# High-Speed-Line-Follower.net
KiCad netlist of a schematic drawn in Altium Designer
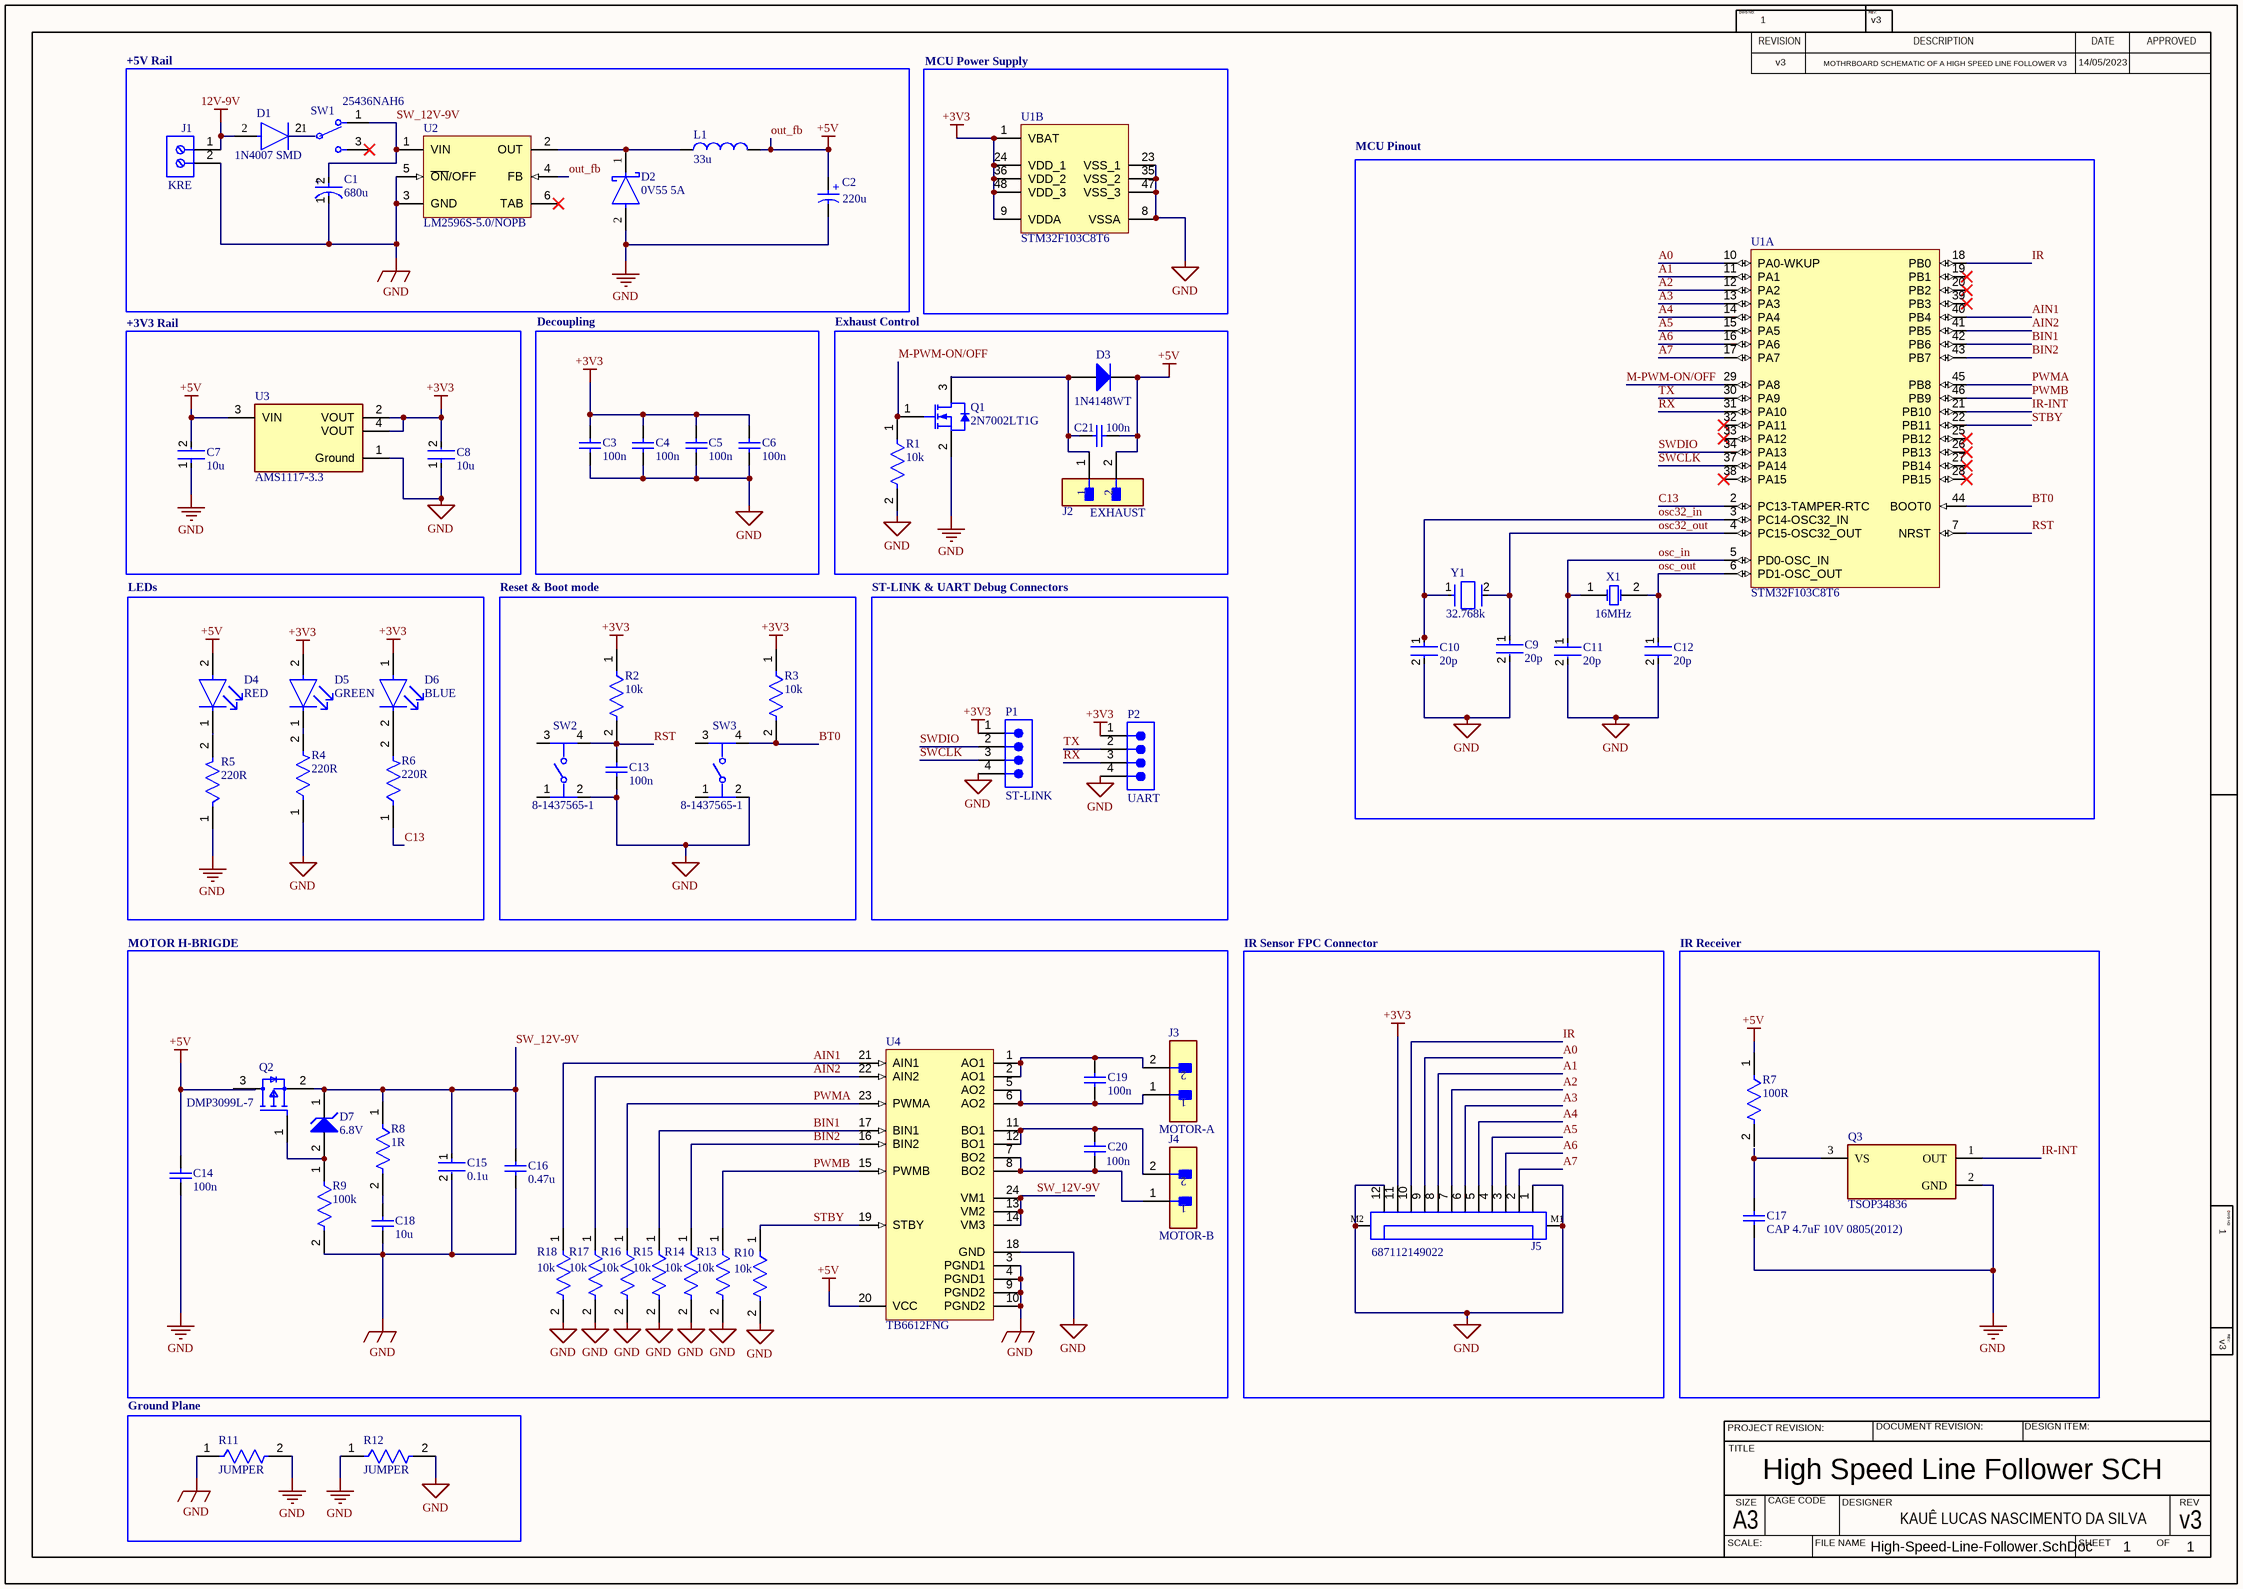
[diagram p0: High-Speed-Line-Follower.SchDoc]

(export (version "E")
  (design (tool "Eeschema 10.0.6"))
  (components
    (comp (ref "C1")
      (value "680u")
      (footprint "FP-OS-CON-SMT-E12-MFG")
      (description "Conductive Polymer Aluminum Solid Capacitors (OS-CON) 680uF ±20% 16V")
      (fields (field (name "TOLERANCE") "20%"))
      (libsource (lib "Altium Content Vault") (part "a00bbbee19879c290e62620ae7e47b1"))
    )
    (comp (ref "C2")
      (value "220u")
      (footprint "WCAP-ASLI_D6.3H7.7")
      (description "WCAP-ASLI Aluminum Electrolytic Capacitors")
      (libsource (lib "Altium Content Vault") (part "Capacitor_Polarized"))
    )
    (comp (ref "C3")
      (value "100n")
      (footprint "CAPC2013X145X50ML20T20")
      (fields (field (name "MANUFACTURER") "Vitramon") (field (name "PART NUMBER") "VJ0805Y104JXXCW1BC"))
      (libsource (lib "Altium Content Vault") (part "CAP"))
    )
    (comp (ref "C4")
      (value "100n")
      (footprint "CAPC2013X145X50ML20T20")
      (fields (field (name "MANUFACTURER") "Vitramon") (field (name "PART NUMBER") "VJ0805Y104JXXCW1BC"))
      (libsource (lib "Altium Content Vault") (part "CAP"))
    )
    (comp (ref "C5")
      (value "100n")
      (footprint "CAPC2013X145X50ML20T20")
      (fields (field (name "MANUFACTURER") "Vitramon") (field (name "PART NUMBER") "VJ0805Y104JXXCW1BC"))
      (libsource (lib "Altium Content Vault") (part "CAP"))
    )
    (comp (ref "C6")
      (value "100n")
      (footprint "CAPC2013X145X50ML20T20")
      (fields (field (name "MANUFACTURER") "Vitramon") (field (name "PART NUMBER") "VJ0805Y104JXXCW1BC"))
      (libsource (lib "Altium Content Vault") (part "CAP"))
    )
    (comp (ref "C7")
      (value "10u")
      (footprint "FP-C0805C106K8RACAUTO-MFG")
      (description "CAP CER 10UF 10V X7R 0805")
      (fields (field (name "TOLERANCE") "10%"))
      (libsource (lib "Altium Content Vault") (part "b4654b650e69147ec39a6b967a45e02"))
    )
    (comp (ref "C8")
      (value "10u")
      (footprint "FP-C0805C106K8RACAUTO-MFG")
      (description "CAP CER 10UF 10V X7R 0805")
      (fields (field (name "TOLERANCE") "10%"))
      (libsource (lib "Altium Content Vault") (part "b4654b650e69147ec39a6b967a45e02"))
    )
    (comp (ref "C9")
      (value "20p")
      (footprint "FP-C0805C-DN-MFG")
      (description "C0805 20 pF X8R 30ppm/°C 2.00% 10 V")
      (fields
        (field (name "OCTOPART") "https://octopart.com/c0805c200g8hactu-kemet-88726762")
        (field (name "TOLERANCE") "0.02")
      )
      (libsource (lib "Altium Content Vault") (part "b4654b650e69147ec39a6b967a45e02"))
    )
    (comp (ref "C10")
      (value "20p")
      (footprint "FP-C0805C-DN-MFG")
      (description "C0805 20 pF X8R 30ppm/°C 2.00% 10 V")
      (fields
        (field (name "OCTOPART") "https://octopart.com/c0805c200g8hactu-kemet-88726762")
        (field (name "TOLERANCE") "0.02")
      )
      (libsource (lib "Altium Content Vault") (part "b4654b650e69147ec39a6b967a45e02"))
    )
    (comp (ref "C11")
      (value "20p")
      (footprint "FP-C0805C-DN-MFG")
      (description "C0805 20 pF X8R 30ppm/°C 2.00% 10 V")
      (fields
        (field (name "OCTOPART") "https://octopart.com/c0805c200g8hactu-kemet-88726762")
        (field (name "TOLERANCE") "0.02")
      )
      (libsource (lib "Altium Content Vault") (part "b4654b650e69147ec39a6b967a45e02"))
    )
    (comp (ref "C12")
      (value "20p")
      (footprint "FP-C0805C-DN-MFG")
      (description "C0805 20 pF X8R 30ppm/°C 2.00% 10 V")
      (fields
        (field (name "OCTOPART") "https://octopart.com/c0805c200g8hactu-kemet-88726762")
        (field (name "TOLERANCE") "0.02")
      )
      (libsource (lib "Altium Content Vault") (part "b4654b650e69147ec39a6b967a45e02"))
    )
    (comp (ref "C13")
      (value "100n")
      (footprint "CAPC2013X140X45LL15T25")
      (fields (field (name "PART NUMBER") "GCM21BR71E104KA37L") (field (name "MANUFACTURER") "Murata"))
      (libsource (lib "Altium Content Vault") (part "CAP"))
    )
    (comp (ref "C14")
      (value "100n")
      (footprint "CAPC2013X140X45LL15T25")
      (fields (field (name "PART NUMBER") "GCM21BR71E104KA37L") (field (name "MANUFACTURER") "Murata"))
      (libsource (lib "Altium Content Vault") (part "CAP"))
    )
    (comp (ref "C15")
      (value "0.1u")
      (footprint "FP-C0805C-DN-MFG")
      (description "CAP CER 0.1UF 50V X7R 0805")
      (fields
        (field (name "MANUFACTURER PART NUMBER") "C0805C104K5RACTU")
        (field (name "MANUFACTURER") "KEMET")
      )
      (libsource (lib "Altium Content Vault") (part "b4654b650e69147ec39a6b967a45e02"))
    )
    (comp (ref "C16")
      (value "0.47u")
      (footprint "CAPC2013X140X50ML20T25")
      (fields (field (name "PART NUMBER") "C0805C474K3NACTU") (field (name "MANUFACTURER") "Kemet"))
      (libsource (lib "Altium Content Vault") (part "CAP"))
    )
    (comp (ref "C17")
      (value "CAP 4.7uF 10V 0805(2012)")
      (footprint "CAPC0805(2012)155_L")
      (description "CAP 4.7uF 10V ±10% 0805 (2012 Metric) Thickness 1.55mm SMD")
      (fields (field (name "TOLERANCE") "Â±10%"))
      (libsource (lib "Altium Content Vault") (part "CAP"))
    )
    (comp (ref "C18")
      (value "10u")
      (footprint "CAPC2013X145X50ML20T25")
      (fields (field (name "PART NUMBER") "C0805C106M4PACTU") (field (name "MANUFACTURER") "Kemet"))
      (libsource (lib "Altium Content Vault") (part "CAP"))
    )
    (comp (ref "C19")
      (value "100n")
      (footprint "CAPC2013X140X45LL15T25")
      (fields (field (name "PART NUMBER") "GCM21BR71E104KA37L") (field (name "MANUFACTURER") "Murata"))
      (libsource (lib "Altium Content Vault") (part "CAP"))
    )
    (comp (ref "C20")
      (value "100n")
      (footprint "CAPC2013X140X45LL15T25")
      (fields (field (name "PART NUMBER") "GCM21BR71E104KA37L") (field (name "MANUFACTURER") "Murata"))
      (libsource (lib "Altium Content Vault") (part "CAP"))
    )
    (comp (ref "C21")
      (value "100n")
      (footprint "CAPC2013X140X45LL15T25")
      (fields (field (name "PART NUMBER") "GCM21BR71E104KA37L") (field (name "MANUFACTURER") "Murata"))
      (libsource (lib "Altium Content Vault") (part "CAP"))
    )
    (comp (ref "D1")
      (value "1N4007 SMD")
      (footprint "FP-1N4007_SMD-IPC_C")
      (description "Rectifier, 1Kv, 1A, Do-214Ac Rohs Compliant: Yes")
      (libsource (lib "Altium Content Vault") (part "d7152d700b627762746794eb795d46e"))
    )
    (comp (ref "D2")
      (value "0V55 5A")
      (footprint "FP-DO-214AA-MFG")
      (description "5819SMJE3/TR13 Rectifier Diode, Schottky, 1 Phase, 1 Element, 1A, 40V V(RRM), Silicon")
      (libsource (lib "Altium Content Vault") (part "1d6ec82d83fb6aee721767c19dac4b9"))
    )
    (comp (ref "D3")
      (value "1N4148WT")
      (footprint "FAIR-SOD-523F-2_V")
      (description "High Conductance Fast Switching Diode, 75 V, -55 to 150 degC, 2-Pin SOD523F, RoHS")
      (fields (field (name "MANUFACTURER") "Fairchild Semiconductor"))
      (libsource (lib "Altium Content Vault") (part "FAIR-D_K1A2-2"))
    )
    (comp (ref "D4")
      (value "RED")
      (footprint "FP-SML-LXT0805IW-TR-MFG")
      (description "LED RED DIFFUSED SMD")
      (libsource (lib "Altium Content Vault") (part "8706943c75ba83719d021d2fdc84c58"))
    )
    (comp (ref "D5")
      (value "GREEN")
      (footprint "FP-LTST-C171GKT-MFG")
      (description "LED GREEN CLEAR CHIP SMD")
      (libsource (lib "Altium Content Vault") (part "8706943c75ba83719d021d2fdc84c58"))
    )
    (comp (ref "D6")
      (value "BLUE")
      (footprint "FP-SM0805UBWC-MFG")
      (description "LED BLUE CLEAR 0805 SMD")
      (libsource (lib "Altium Content Vault") (part "ab1c01a81903e929fc6c44469aada92"))
    )
    (comp (ref "D7")
      (value "6.8V")
      (footprint "ONSC-SMB-2-403A-03_H_V")
      (description "3 W Zener Voltage Regulator, 2-Pin SMB, Pb-Free, Tape and Reel")
      (fields (field (name "PARTNUMBER") "1SMB5921BT3G") (field (name "MANUFACTURER") "On Semiconductor"))
      (libsource (lib "Altium Content Vault") (part "ONSC-K1A2-2"))
    )
    (comp (ref "J1")
      (value "KRE")
      (footprint "691502710002")
      (description "Terminal Block, Wtb, 2Way, 22-14Awg Rohs Compliant: Yes")
      (libsource (lib "Altium Content Vault") (part "TBL - 1R - 02P - Screw"))
    )
    (comp (ref "J2")
      (value "EXHAUST")
      (footprint "FP-B2B-XH-A_LF_SN-MFG")
      (description "CONN HEADER VERT 2POS 2.5MM")
      (libsource (lib "Altium Content Vault") (part "3bc925449376181038e59eaffc5286c"))
    )
    (comp (ref "J3")
      (value "MOTOR-A")
      (footprint "FP-B2B-XH-A_LF_SN-MFG")
      (description "CONN HEADER VERT 2POS 2.5MM")
      (libsource (lib "") (part "3bc925449376181038e59eaffc5286c_1"))
    )
    (comp (ref "J4")
      (value "MOTOR-B")
      (footprint "FP-B2B-XH-A_LF_SN-MFG")
      (description "CONN HEADER VERT 2POS 2.5MM")
      (libsource (lib "") (part "3bc925449376181038e59eaffc5286c_1"))
    )
    (comp (ref "J5")
      (value "687112149022")
      (footprint "687112149022")
      (description "FFC/FPC Connector, 12 Contact(s), 1 Row(s), Female, Right Angle, Surface Mount Terminal")
      (libsource (lib "Altium Content Vault") (part "FPC - 12P - 2MP"))
    )
    (comp (ref "L1")
      (value "33u")
      (footprint "SUMI-CDRH127_V")
      (description "Power Inductor, 10 uH, +/- 20%, -40 to 100 degC, 2-Pin SMD, RoHS, Tape and Reel")
      (fields (field (name "MANUFACTURER") "Sumida") (field (name "TOLERANCE") "±20%"))
      (libsource (lib "Altium Content Vault") (part "IND-2"))
    )
    (comp (ref "P1")
      (value "ST-LINK")
      (footprint "61300411121")
      (description "THT Vertical Pin Header WR-PHD, Pitch 2.54 mm, Single Row, 4 pins")
      (libsource (lib "Altium Content Vault") (part "Header_Male_1R_04P"))
    )
    (comp (ref "P2")
      (value "UART")
      (footprint "61300411121")
      (description "THT Vertical Pin Header WR-PHD, Pitch 2.54 mm, Single Row, 4 pins")
      (libsource (lib "Altium Content Vault") (part "Header_Male_1R_04P"))
    )
    (comp (ref "Q1")
      (value "2N7002LT1G")
      (footprint "ONSC-SOT-23-3-318-08_V")
      (description "Small Signal MOSFET, 60 V, 115 mA, N-Channel, 3-Pin SOT-23, Pb-Free, Tape and Reel")
      (fields (field (name "MANUFACTURER") "On Semiconductor"))
      (libsource (lib "Altium Content Vault") (part "ONSC-NMOS-G1S2D3-3"))
    )
    (comp (ref "Q2")
      (value "DMP3099L-7")
      (footprint "FP-SOT23-IPC_B")
      (description "MOSFET P-CH 30V SOT23")
      (libsource (lib "Altium Content Vault") (part "d876440acba04c58a9f817a20952145"))
    )
    (comp (ref "Q3")
      (value "TSOP34836")
      (footprint "FP-6_550-5169_01-4-MFG")
      (description "TSOP34836 TSOP348 Series 2.5 to 5.5 V 36 KHz 350 uA 45 m Side View IR Receiver")
      (libsource (lib "Altium Content Vault") (part "e5e79ff3c4dc99b7cd60a318e631326"))
    )
    (comp (ref "R1")
      (value "10k")
      (footprint "FP-CRGCQ0805-IPC_C")
      (description "CRGCQ 0805 10K 5%")
      (fields
        (field (name "MANUFACTURER PART NUMBER") "CRGCQ0805J10K")
        (field (name "MANUFACTURER") "TE Connectivity")
      )
      (libsource (lib "Altium Content Vault") (part "1029c3af85768c4190bb7ad29bc67b5"))
    )
    (comp (ref "R2")
      (value "10k")
      (footprint "FP-CRGCQ0805-IPC_C")
      (description "CRGCQ 0805 10K 5%")
      (fields
        (field (name "MANUFACTURER PART NUMBER") "CRGCQ0805J10K")
        (field (name "MANUFACTURER") "TE Connectivity")
      )
      (libsource (lib "Altium Content Vault") (part "1029c3af85768c4190bb7ad29bc67b5"))
    )
    (comp (ref "R3")
      (value "10k")
      (footprint "FP-CRGCQ0805-IPC_C")
      (description "CRGCQ 0805 10K 5%")
      (fields
        (field (name "MANUFACTURER PART NUMBER") "CRGCQ0805J10K")
        (field (name "MANUFACTURER") "TE Connectivity")
      )
      (libsource (lib "Altium Content Vault") (part "1029c3af85768c4190bb7ad29bc67b5"))
    )
    (comp (ref "R4")
      (value "220R")
      (footprint "FP-AC0805-MFG")
      (description "RES SMD 220 OHM 1% 1/8W 0805")
      (fields
        (field (name "OCTOPART") "https://octopart.com/ac0805fr-07220rl-yageo-26041145")
        (field (name "TOLERANCE") "0.01")
      )
      (libsource (lib "Altium Content Vault") (part "1029c3af85768c4190bb7ad29bc67b5"))
    )
    (comp (ref "R5")
      (value "220R")
      (footprint "FP-AC0805-MFG")
      (description "RES SMD 220 OHM 1% 1/8W 0805")
      (fields
        (field (name "OCTOPART") "https://octopart.com/ac0805fr-07220rl-yageo-26041145")
        (field (name "TOLERANCE") "0.01")
      )
      (libsource (lib "Altium Content Vault") (part "1029c3af85768c4190bb7ad29bc67b5"))
    )
    (comp (ref "R6")
      (value "220R")
      (footprint "FP-AC0805-MFG")
      (description "RES SMD 220 OHM 1% 1/8W 0805")
      (fields
        (field (name "OCTOPART") "https://octopart.com/ac0805fr-07220rl-yageo-26041145")
        (field (name "TOLERANCE") "0.01")
      )
      (libsource (lib "Altium Content Vault") (part "1029c3af85768c4190bb7ad29bc67b5"))
    )
    (comp (ref "R7")
      (value "100R")
      (footprint "FP-CRCW0805-HPe3-IPC_C")
      (description "RES Thick Film, 100Ω, 5%, 0.5W, 200ppm/°C, 0805")
      (fields (field (name "TOLERANCE") "5%"))
      (libsource (lib "Altium Content Vault") (part "1029c3af85768c4190bb7ad29bc67b5"))
    )
    (comp (ref "R8")
      (value "1R")
      (footprint "FP-CRCW0805-e3-IPC_C")
      (description "RES Thick Film, 1Ω, 5%, 0.125W, 200ppm/°C, 0805")
      (fields (field (name "TOLERANCE") "5%"))
      (libsource (lib "Altium Content Vault") (part "1029c3af85768c4190bb7ad29bc67b5"))
    )
    (comp (ref "R9")
      (value "100k")
      (footprint "FP-MCU0805-IPC_C")
      (description "RES 1.05K OHM 0.5% 1/5W 0805")
      (fields (field (name "TOLERANCE") "1%"))
      (libsource (lib "Altium Content Vault") (part "1029c3af85768c4190bb7ad29bc67b5"))
    )
    (comp (ref "R10")
      (value "10k")
      (footprint "FP-CRGCQ0805-IPC_C")
      (description "CRGCQ 0805 10K 5%")
      (fields
        (field (name "MANUFACTURER PART NUMBER") "CRGCQ0805J10K")
        (field (name "MANUFACTURER") "TE Connectivity")
      )
      (libsource (lib "Altium Content Vault") (part "1029c3af85768c4190bb7ad29bc67b5"))
    )
    (comp (ref "R11")
      (value "JUMPER")
      (footprint "FP-HCJ0805-MFG")
      (description "RES 0 OHM JUMPER 1/2W 0805")
      (libsource (lib "Altium Content Vault") (part "1029c3af85768c4190bb7ad29bc67b5"))
    )
    (comp (ref "R12")
      (value "JUMPER")
      (footprint "FP-HCJ0805-MFG")
      (description "RES 0 OHM JUMPER 1/2W 0805")
      (libsource (lib "Altium Content Vault") (part "1029c3af85768c4190bb7ad29bc67b5"))
    )
    (comp (ref "R13")
      (value "10k")
      (footprint "FP-CRGCQ0805-IPC_C")
      (description "CRGCQ 0805 10K 5%")
      (fields
        (field (name "MANUFACTURER PART NUMBER") "CRGCQ0805J10K")
        (field (name "MANUFACTURER") "TE Connectivity")
      )
      (libsource (lib "Altium Content Vault") (part "1029c3af85768c4190bb7ad29bc67b5"))
    )
    (comp (ref "R14")
      (value "10k")
      (footprint "FP-CRGCQ0805-IPC_C")
      (description "CRGCQ 0805 10K 5%")
      (fields
        (field (name "MANUFACTURER PART NUMBER") "CRGCQ0805J10K")
        (field (name "MANUFACTURER") "TE Connectivity")
      )
      (libsource (lib "Altium Content Vault") (part "1029c3af85768c4190bb7ad29bc67b5"))
    )
    (comp (ref "R15")
      (value "10k")
      (footprint "FP-CRGCQ0805-IPC_C")
      (description "CRGCQ 0805 10K 5%")
      (fields
        (field (name "MANUFACTURER PART NUMBER") "CRGCQ0805J10K")
        (field (name "MANUFACTURER") "TE Connectivity")
      )
      (libsource (lib "Altium Content Vault") (part "1029c3af85768c4190bb7ad29bc67b5"))
    )
    (comp (ref "R16")
      (value "10k")
      (footprint "FP-CRGCQ0805-IPC_C")
      (description "CRGCQ 0805 10K 5%")
      (fields
        (field (name "MANUFACTURER PART NUMBER") "CRGCQ0805J10K")
        (field (name "MANUFACTURER") "TE Connectivity")
      )
      (libsource (lib "Altium Content Vault") (part "1029c3af85768c4190bb7ad29bc67b5"))
    )
    (comp (ref "R17")
      (value "10k")
      (footprint "FP-CRGCQ0805-IPC_C")
      (description "CRGCQ 0805 10K 5%")
      (fields
        (field (name "MANUFACTURER PART NUMBER") "CRGCQ0805J10K")
        (field (name "MANUFACTURER") "TE Connectivity")
      )
      (libsource (lib "Altium Content Vault") (part "1029c3af85768c4190bb7ad29bc67b5"))
    )
    (comp (ref "R18")
      (value "10k")
      (footprint "FP-CRGCQ0805-IPC_C")
      (description "CRGCQ 0805 10K 5%")
      (fields
        (field (name "MANUFACTURER PART NUMBER") "CRGCQ0805J10K")
        (field (name "MANUFACTURER") "TE Connectivity")
      )
      (libsource (lib "Altium Content Vault") (part "1029c3af85768c4190bb7ad29bc67b5"))
    )
    (comp (ref "SW1")
      (value "25436NAH6")
      (footprint "FP-25436NAH6-MFG")
      (description "SWITCH SLIDE SPDT 4A 125V")
      (libsource (lib "Altium Content Vault") (part "52c419afdc2a387c7d548259a9aeefb"))
    )
    (comp (ref "SW2")
      (value "8-1437565-1")
      (footprint "FP-8-1437565-1-MFG")
      (description "SWITCH TACTILE SPST-NO 0.02A 15V")
      (libsource (lib "Altium Content Vault") (part "b8895f3f4cefb76e1819d2863dba89b"))
    )
    (comp (ref "SW3")
      (value "8-1437565-1")
      (footprint "FP-8-1437565-1-MFG")
      (description "SWITCH TACTILE SPST-NO 0.02A 15V")
      (libsource (lib "Altium Content Vault") (part "b8895f3f4cefb76e1819d2863dba89b"))
    )
    (comp (ref "U1")
      (value "STM32F103C8T6")
      (footprint "STM-LQFP48_L")
      (libsource (lib "Altium Content Vault") (part "MC-ARM-STM32F103X8_B-SQ48"))
    )
    (comp (ref "U2")
      (value "LM2596S-5.0/NOPB")
      (footprint "KTT0005B_M")
      (description "SIMPLE SWITCHER® Power Converter 150 KHz 3A Step-Down Voltage Regulator, 5-pin TO-263, Pb-Free")
      (fields (field (name "MANUFACTURER") "Texas Instruments"))
      (libsource (lib "Altium Content Vault") (part "PM-REG-LM2575HVS-12"))
    )
    (comp (ref "U3")
      (value "AMS1117-3.3")
      (footprint "FP-AMS1117-IPC_C")
      (description "LDO Voltage Regulators 1A, 3.3V")
      (fields
        (field (name "OCTOPART") "https://octopart.com/ams1117-3.3-advanced+monolithic+systems-25899300")
        (field (name "MANUFACTURER") "Advanced Monolithic Systems")
      )
      (libsource (lib "Altium Content Vault") (part "8bdbb5f8e77002000e30dd2845d0354"))
    )
    (comp (ref "U4")
      (value "TB6612FNG")
      (footprint "TOSH-SSOP-24_M")
      (description "Driver IC for Dual DC Motor, 15 V, -20 to 85 degC, 24-Pin SSOP, RoHS, Tape and Reel")
      (libsource (lib "Altium Content Vault") (part "TOSH-TB6612FNG-SOP-24"))
    )
    (comp (ref "X1")
      (value "16MHz")
      (footprint "CTS-ATS-SM-XTAL-2")
      (description "ATS-SM Series Quartz Crystal, 16 MHz, -20 to 70 degC, 11.1 x 4.83 x 4.3mm SMD, RoHS, Tape and Reel")
      (fields (field (name "PARTNUMBER") "ATS16ASM-1") (field (name "MANUFACTURER") "CTS Corporation"))
      (libsource (lib "Altium Content Vault") (part "CTS-ATS-SM-XTAL-2"))
    )
    (comp (ref "Y1")
      (value "32.768k")
      (footprint "FP-NX2012SA-MFG")
      (description "CRYSTAL 32.7680KHZ 12.5PF SMD")
      (libsource (lib "Altium Content Vault") (part "c23a69dc6c9e2f18f2079038eb95dd1"))
    )
  )
  (nets
    (net (code "1") (name "+3V3") (class "Default")
      (node (ref "C3") (pin "2") (pinfunction "2_2") (pintype "passive"))
      (node (ref "C4") (pin "2") (pinfunction "2_2") (pintype "passive"))
      (node (ref "C5") (pin "2") (pinfunction "2_2") (pintype "passive"))
      (node (ref "C6") (pin "2") (pinfunction "2_2") (pintype "passive"))
      (node (ref "C8") (pin "2") (pinfunction "2_2") (pintype "passive"))
      (node (ref "D6") (pin "1") (pinfunction "A_1") (pintype "passive"))
      (node (ref "J5") (pin "11") (pinfunction "11_11") (pintype "passive"))
      (node (ref "P1") (pin "1") (pinfunction "1_1") (pintype "passive"))
      (node (ref "P2") (pin "1") (pinfunction "1_1") (pintype "passive"))
      (node (ref "R2") (pin "1") (pinfunction "1_1") (pintype "passive"))
      (node (ref "R3") (pin "1") (pinfunction "1_1") (pintype "passive"))
      (node (ref "U1") (pin "1") (pinfunction "VBAT_1") (pintype "power_in"))
      (node (ref "U1") (pin "24") (pinfunction "VDD_1_24") (pintype "power_in"))
      (node (ref "U1") (pin "36") (pinfunction "VDD_2_36") (pintype "power_in"))
      (node (ref "U1") (pin "48") (pinfunction "VDD_3_48") (pintype "power_in"))
      (node (ref "U1") (pin "9") (pinfunction "VDDA_9") (pintype "power_in"))
      (node (ref "U3") (pin "2") (pinfunction "VOUT_2") (pintype "passive"))
      (node (ref "U3") (pin "4") (pinfunction "VOUT_4") (pintype "passive"))
    )
    (net (code "2") (name "+5V") (class "Default")
      (node (ref "C14") (pin "2") (pinfunction "2_2") (pintype "passive"))
      (node (ref "C2") (pin "1") (pinfunction "P_1") (pintype "passive"))
      (node (ref "C21") (pin "1") (pinfunction "1_1") (pintype "passive"))
      (node (ref "C7") (pin "2") (pinfunction "2_2") (pintype "passive"))
      (node (ref "D3") (pin "1") (pinfunction "K_1") (pintype "passive"))
      (node (ref "D4") (pin "2") (pinfunction "A_2") (pintype "passive"))
      (node (ref "J2") (pin "2") (pinfunction "2_2") (pintype "passive"))
      (node (ref "L1") (pin "2") (pinfunction "2_2") (pintype "passive"))
      (node (ref "R7") (pin "1") (pinfunction "1_1") (pintype "passive"))
      (node (ref "U2") (pin "4") (pinfunction "FB_4") (pintype "input"))
      (node (ref "U3") (pin "3") (pinfunction "VIN_3") (pintype "power_in"))
      (node (ref "U4") (pin "20") (pinfunction "VCC_20") (pintype "power_in"))
    )
    (net (code "3") (name "/A0") (class "Default")
      (node (ref "J5") (pin "9") (pinfunction "9_9") (pintype "passive"))
      (node (ref "U1") (pin "10") (pinfunction "PA0-WKUP_10") (pintype "bidirectional"))
    )
    (net (code "4") (name "/A1") (class "Default")
      (node (ref "J5") (pin "8") (pinfunction "8_8") (pintype "passive"))
      (node (ref "U1") (pin "11") (pinfunction "PA1_11") (pintype "bidirectional"))
    )
    (net (code "5") (name "/A2") (class "Default")
      (node (ref "J5") (pin "7") (pinfunction "7_7") (pintype "passive"))
      (node (ref "U1") (pin "12") (pinfunction "PA2_12") (pintype "bidirectional"))
    )
    (net (code "6") (name "/A3") (class "Default")
      (node (ref "J5") (pin "6") (pinfunction "6_6") (pintype "passive"))
      (node (ref "U1") (pin "13") (pinfunction "PA3_13") (pintype "bidirectional"))
    )
    (net (code "7") (name "/A4") (class "Default")
      (node (ref "J5") (pin "5") (pinfunction "5_5") (pintype "passive"))
      (node (ref "U1") (pin "14") (pinfunction "PA4_14") (pintype "bidirectional"))
    )
    (net (code "8") (name "/A5") (class "Default")
      (node (ref "J5") (pin "4") (pinfunction "4_4") (pintype "passive"))
      (node (ref "U1") (pin "15") (pinfunction "PA5_15") (pintype "bidirectional"))
    )
    (net (code "9") (name "/A6") (class "Default")
      (node (ref "J5") (pin "3") (pinfunction "3_3") (pintype "passive"))
      (node (ref "U1") (pin "16") (pinfunction "PA6_16") (pintype "bidirectional"))
    )
    (net (code "10") (name "/A7") (class "Default")
      (node (ref "J5") (pin "2") (pinfunction "2_2") (pintype "passive"))
      (node (ref "U1") (pin "17") (pinfunction "PA7_17") (pintype "bidirectional"))
    )
    (net (code "11") (name "/AIN1") (class "Default")
      (node (ref "R18") (pin "1") (pinfunction "1_1") (pintype "passive"))
      (node (ref "U1") (pin "40") (pinfunction "PB4_40") (pintype "bidirectional"))
      (node (ref "U4") (pin "21") (pinfunction "AIN1_21") (pintype "input"))
    )
    (net (code "12") (name "/AIN2") (class "Default")
      (node (ref "R17") (pin "1") (pinfunction "1_1") (pintype "passive"))
      (node (ref "U1") (pin "41") (pinfunction "PB5_41") (pintype "bidirectional"))
      (node (ref "U4") (pin "22") (pinfunction "AIN2_22") (pintype "input"))
    )
    (net (code "13") (name "/BIN1") (class "Default")
      (node (ref "R15") (pin "1") (pinfunction "1_1") (pintype "passive"))
      (node (ref "U1") (pin "42") (pinfunction "PB6_42") (pintype "bidirectional"))
      (node (ref "U4") (pin "17") (pinfunction "BIN1_17") (pintype "input"))
    )
    (net (code "14") (name "/BIN2") (class "Default")
      (node (ref "R14") (pin "1") (pinfunction "1_1") (pintype "passive"))
      (node (ref "U1") (pin "43") (pinfunction "PB7_43") (pintype "bidirectional"))
      (node (ref "U4") (pin "16") (pinfunction "BIN2_16") (pintype "input"))
    )
    (net (code "15") (name "/BT0") (class "Default")
      (node (ref "R3") (pin "2") (pinfunction "2_2") (pintype "passive"))
      (node (ref "SW3") (pin "4") (pinfunction "4_4") (pintype "passive"))
      (node (ref "U1") (pin "44") (pinfunction "BOOT0_44") (pintype "input"))
    )
    (net (code "16") (name "/C13") (class "Default")
      (node (ref "R6") (pin "1") (pinfunction "1_1") (pintype "passive"))
      (node (ref "U1") (pin "2") (pinfunction "PC13-TAMPER-RTC_2") (pintype "bidirectional"))
    )
    (net (code "17") (name "/IR") (class "Default")
      (node (ref "J5") (pin "10") (pinfunction "10_10") (pintype "passive"))
      (node (ref "U1") (pin "18") (pinfunction "PB0_18") (pintype "bidirectional"))
    )
    (net (code "18") (name "/IR-INT") (class "Default")
      (node (ref "Q3") (pin "1") (pinfunction "OUT_1") (pintype "passive"))
      (node (ref "U1") (pin "21") (pinfunction "PB10_21") (pintype "bidirectional"))
    )
    (net (code "19") (name "/M-PWM-ON{slash}OFF") (class "Default")
      (node (ref "Q1") (pin "1") (pinfunction "G_1") (pintype "passive"))
      (node (ref "R1") (pin "1") (pinfunction "1_1") (pintype "passive"))
      (node (ref "U1") (pin "29") (pinfunction "PA8_29") (pintype "bidirectional"))
    )
    (net (code "20") (name "/PWMA") (class "Default")
      (node (ref "R16") (pin "1") (pinfunction "1_1") (pintype "passive"))
      (node (ref "U1") (pin "45") (pinfunction "PB8_45") (pintype "bidirectional"))
      (node (ref "U4") (pin "23") (pinfunction "PWMA_23") (pintype "input"))
    )
    (net (code "21") (name "/PWMB") (class "Default")
      (node (ref "R13") (pin "1") (pinfunction "1_1") (pintype "passive"))
      (node (ref "U1") (pin "46") (pinfunction "PB9_46") (pintype "bidirectional"))
      (node (ref "U4") (pin "15") (pinfunction "PWMB_15") (pintype "input"))
    )
    (net (code "22") (name "/RST") (class "Default")
      (node (ref "C13") (pin "2") (pinfunction "2_2") (pintype "passive"))
      (node (ref "R2") (pin "2") (pinfunction "2_2") (pintype "passive"))
      (node (ref "SW2") (pin "4") (pinfunction "4_4") (pintype "passive"))
      (node (ref "U1") (pin "7") (pinfunction "NRST_7") (pintype "bidirectional"))
    )
    (net (code "23") (name "/RX") (class "Default")
      (node (ref "P2") (pin "3") (pinfunction "3_3") (pintype "passive"))
      (node (ref "U1") (pin "31") (pinfunction "PA10_31") (pintype "bidirectional"))
    )
    (net (code "24") (name "/STBY") (class "Default")
      (node (ref "R10") (pin "1") (pinfunction "1_1") (pintype "passive"))
      (node (ref "U1") (pin "22") (pinfunction "PB11_22") (pintype "bidirectional"))
      (node (ref "U4") (pin "19") (pinfunction "STBY_19") (pintype "input"))
    )
    (net (code "25") (name "/SWCLK") (class "Default")
      (node (ref "P1") (pin "3") (pinfunction "3_3") (pintype "passive"))
      (node (ref "U1") (pin "37") (pinfunction "PA14_37") (pintype "bidirectional"))
    )
    (net (code "26") (name "/SWDIO") (class "Default")
      (node (ref "P1") (pin "2") (pinfunction "2_2") (pintype "passive"))
      (node (ref "U1") (pin "34") (pinfunction "PA13_34") (pintype "bidirectional"))
    )
    (net (code "27") (name "/SW_12V-9V") (class "Default")
      (node (ref "C1") (pin "2") (pinfunction "A_2") (pintype "passive"))
      (node (ref "C15") (pin "1") (pinfunction "1_1") (pintype "passive"))
      (node (ref "C16") (pin "2") (pinfunction "2_2") (pintype "passive"))
      (node (ref "D7") (pin "1") (pinfunction "K_1") (pintype "passive"))
      (node (ref "Q2") (pin "2") (pinfunction "S_2") (pintype "passive"))
      (node (ref "R8") (pin "1") (pinfunction "1_1") (pintype "passive"))
      (node (ref "SW1") (pin "1") (pinfunction "1_1") (pintype "passive"))
      (node (ref "U2") (pin "1") (pinfunction "VIN_1") (pintype "power_in"))
      (node (ref "U4") (pin "13") (pinfunction "VM2_13") (pintype "power_in"))
      (node (ref "U4") (pin "14") (pinfunction "VM3_14") (pintype "power_in"))
      (node (ref "U4") (pin "24") (pinfunction "VM1_24") (pintype "power_in"))
    )
    (net (code "28") (name "/TX") (class "Default")
      (node (ref "P2") (pin "2") (pinfunction "2_2") (pintype "passive"))
      (node (ref "U1") (pin "30") (pinfunction "PA9_30") (pintype "bidirectional"))
    )
    (net (code "29") (name "/osc32_in") (class "Default")
      (node (ref "C10") (pin "1") (pinfunction "1_1") (pintype "passive"))
      (node (ref "U1") (pin "3") (pinfunction "PC14-OSC32_IN_3") (pintype "bidirectional"))
      (node (ref "Y1") (pin "1") (pinfunction "1_1") (pintype "passive"))
    )
    (net (code "30") (name "/osc32_out") (class "Default")
      (node (ref "C9") (pin "1") (pinfunction "1_1") (pintype "passive"))
      (node (ref "U1") (pin "4") (pinfunction "PC15-OSC32_OUT_4") (pintype "bidirectional"))
      (node (ref "Y1") (pin "2") (pinfunction "2_2") (pintype "passive"))
    )
    (net (code "31") (name "/osc_in") (class "Default")
      (node (ref "C11") (pin "1") (pinfunction "1_1") (pintype "passive"))
      (node (ref "U1") (pin "5") (pinfunction "PD0-OSC_IN_5") (pintype "bidirectional"))
      (node (ref "X1") (pin "1") (pinfunction "X1_1") (pintype "passive"))
    )
    (net (code "32") (name "/osc_out") (class "Default")
      (node (ref "C12") (pin "1") (pinfunction "1_1") (pintype "passive"))
      (node (ref "U1") (pin "6") (pinfunction "PD1-OSC_OUT_6") (pintype "bidirectional"))
      (node (ref "X1") (pin "2") (pinfunction "X2_2") (pintype "passive"))
    )
    (net (code "33") (name "12V-9V") (class "Default")
      (node (ref "D1") (pin "2") (pinfunction "A_2") (pintype "passive"))
      (node (ref "J1") (pin "1") (pinfunction "1_1") (pintype "passive"))
    )
    (net (code "34") (name "GND") (class "Default")
      (node (ref "C1") (pin "1") (pinfunction "C_1") (pintype "passive"))
      (node (ref "C10") (pin "2") (pinfunction "2_2") (pintype "passive"))
      (node (ref "C11") (pin "2") (pinfunction "2_2") (pintype "passive"))
      (node (ref "C12") (pin "2") (pinfunction "2_2") (pintype "passive"))
      (node (ref "C13") (pin "1") (pinfunction "1_1") (pintype "passive"))
      (node (ref "C14") (pin "1") (pinfunction "1_1") (pintype "passive"))
      (node (ref "C15") (pin "2") (pinfunction "2_2") (pintype "passive"))
      (node (ref "C16") (pin "1") (pinfunction "1_1") (pintype "passive"))
      (node (ref "C17") (pin "1") (pinfunction "1_1") (pintype "passive"))
      (node (ref "C18") (pin "1") (pinfunction "1_1") (pintype "passive"))
      (node (ref "C2") (pin "2") (pinfunction "N_2") (pintype "passive"))
      (node (ref "C3") (pin "1") (pinfunction "1_1") (pintype "passive"))
      (node (ref "C4") (pin "1") (pinfunction "1_1") (pintype "passive"))
      (node (ref "C5") (pin "1") (pinfunction "1_1") (pintype "passive"))
      (node (ref "C6") (pin "1") (pinfunction "1_1") (pintype "passive"))
      (node (ref "C7") (pin "1") (pinfunction "1_1") (pintype "passive"))
      (node (ref "C8") (pin "1") (pinfunction "1_1") (pintype "passive"))
      (node (ref "C9") (pin "2") (pinfunction "2_2") (pintype "passive"))
      (node (ref "D2") (pin "2") (pinfunction "A_2") (pintype "passive"))
      (node (ref "J1") (pin "2") (pinfunction "2_2") (pintype "passive"))
      (node (ref "J5") (pin "1") (pinfunction "1_1") (pintype "passive"))
      (node (ref "J5") (pin "12") (pinfunction "12_12") (pintype "passive"))
      (node (ref "J5") (pin "M1") (pinfunction "M1_M1") (pintype "passive"))
      (node (ref "J5") (pin "M2") (pinfunction "M2_M2") (pintype "passive"))
      (node (ref "P1") (pin "4") (pinfunction "4_4") (pintype "passive"))
      (node (ref "P2") (pin "4") (pinfunction "4_4") (pintype "passive"))
      (node (ref "Q1") (pin "2") (pinfunction "S_2") (pintype "passive"))
      (node (ref "Q3") (pin "2") (pinfunction "GND_2") (pintype "power_in"))
      (node (ref "R1") (pin "2") (pinfunction "2_2") (pintype "passive"))
      (node (ref "R10") (pin "2") (pinfunction "2_2") (pintype "passive"))
      (node (ref "R11") (pin "1") (pinfunction "1_1") (pintype "passive"))
      (node (ref "R11") (pin "2") (pinfunction "2_2") (pintype "passive"))
      (node (ref "R12") (pin "1") (pinfunction "1_1") (pintype "passive"))
      (node (ref "R12") (pin "2") (pinfunction "2_2") (pintype "passive"))
      (node (ref "R13") (pin "2") (pinfunction "2_2") (pintype "passive"))
      (node (ref "R14") (pin "2") (pinfunction "2_2") (pintype "passive"))
      (node (ref "R15") (pin "2") (pinfunction "2_2") (pintype "passive"))
      (node (ref "R16") (pin "2") (pinfunction "2_2") (pintype "passive"))
      (node (ref "R17") (pin "2") (pinfunction "2_2") (pintype "passive"))
      (node (ref "R18") (pin "2") (pinfunction "2_2") (pintype "passive"))
      (node (ref "R4") (pin "1") (pinfunction "1_1") (pintype "passive"))
      (node (ref "R5") (pin "1") (pinfunction "1_1") (pintype "passive"))
      (node (ref "R9") (pin "2") (pinfunction "2_2") (pintype "passive"))
      (node (ref "SW2") (pin "2") (pinfunction "2_2") (pintype "passive"))
      (node (ref "SW3") (pin "2") (pinfunction "2_2") (pintype "passive"))
      (node (ref "U1") (pin "23") (pinfunction "VSS_1_23") (pintype "power_in"))
      (node (ref "U1") (pin "35") (pinfunction "VSS_2_35") (pintype "power_in"))
      (node (ref "U1") (pin "47") (pinfunction "VSS_3_47") (pintype "power_in"))
      (node (ref "U1") (pin "8") (pinfunction "VSSA_8") (pintype "power_in"))
      (node (ref "U2") (pin "3") (pinfunction "GND_3") (pintype "power_in"))
      (node (ref "U2") (pin "5") (pinfunction "~{ON}/OFF_5") (pintype "input"))
      (node (ref "U3") (pin "1") (pinfunction "Ground_1") (pintype "power_in"))
      (node (ref "U4") (pin "10") (pinfunction "PGND2_10") (pintype "power_in"))
      (node (ref "U4") (pin "18") (pinfunction "GND_18") (pintype "power_in"))
      (node (ref "U4") (pin "3") (pinfunction "PGND1_3") (pintype "power_in"))
      (node (ref "U4") (pin "4") (pinfunction "PGND1_4") (pintype "power_in"))
      (node (ref "U4") (pin "9") (pinfunction "PGND2_9") (pintype "power_in"))
    )
    (net (code "35") (name "Net-(C18-Pad2)") (class "Default")
      (node (ref "C18") (pin "2") (pinfunction "2_2") (pintype "passive"))
      (node (ref "R8") (pin "2") (pinfunction "2_2") (pintype "passive"))
    )
    (net (code "36") (name "Net-(C19-Pad1)") (class "Default")
      (node (ref "C19") (pin "1") (pinfunction "1_1") (pintype "passive"))
      (node (ref "J3") (pin "1") (pinfunction "1_1") (pintype "passive"))
      (node (ref "U4") (pin "5") (pinfunction "AO2_5") (pintype "tri_state"))
      (node (ref "U4") (pin "6") (pinfunction "AO2_6") (pintype "tri_state"))
    )
    (net (code "37") (name "Net-(C19-Pad2)") (class "Default")
      (node (ref "C19") (pin "2") (pinfunction "2_2") (pintype "passive"))
      (node (ref "J3") (pin "2") (pinfunction "2_2") (pintype "passive"))
      (node (ref "U4") (pin "1") (pinfunction "AO1_1") (pintype "tri_state"))
      (node (ref "U4") (pin "2") (pinfunction "AO1_2") (pintype "tri_state"))
    )
    (net (code "38") (name "Net-(C20-Pad1)") (class "Default")
      (node (ref "C20") (pin "1") (pinfunction "1_1") (pintype "passive"))
      (node (ref "J4") (pin "1") (pinfunction "1_1") (pintype "passive"))
      (node (ref "U4") (pin "7") (pinfunction "BO2_7") (pintype "tri_state"))
      (node (ref "U4") (pin "8") (pinfunction "BO2_8") (pintype "tri_state"))
    )
    (net (code "39") (name "Net-(C20-Pad2)") (class "Default")
      (node (ref "C20") (pin "2") (pinfunction "2_2") (pintype "passive"))
      (node (ref "J4") (pin "2") (pinfunction "2_2") (pintype "passive"))
      (node (ref "U4") (pin "11") (pinfunction "BO1_11") (pintype "tri_state"))
      (node (ref "U4") (pin "12") (pinfunction "BO1_12") (pintype "tri_state"))
    )
    (net (code "40") (name "Net-(D1-C)") (class "Default")
      (node (ref "D1") (pin "1") (pinfunction "C_1") (pintype "passive"))
      (node (ref "SW1") (pin "2") (pinfunction "2_2") (pintype "passive"))
    )
    (net (code "41") (name "Net-(D2-C)") (class "Default")
      (node (ref "D2") (pin "1") (pinfunction "C_1") (pintype "passive"))
      (node (ref "L1") (pin "1") (pinfunction "1_1") (pintype "passive"))
      (node (ref "U2") (pin "2") (pinfunction "OUT_2") (pintype "power_in"))
    )
    (net (code "42") (name "Net-(D3-A)") (class "Default")
      (node (ref "C21") (pin "2") (pinfunction "2_2") (pintype "passive"))
      (node (ref "D3") (pin "2") (pinfunction "A_2") (pintype "passive"))
      (node (ref "J2") (pin "1") (pinfunction "1_1") (pintype "passive"))
    )
    (net (code "43") (name "Net-(D4-C)") (class "Default")
      (node (ref "D4") (pin "1") (pinfunction "C_1") (pintype "passive"))
      (node (ref "R5") (pin "2") (pinfunction "2_2") (pintype "passive"))
    )
    (net (code "44") (name "Net-(D5-C)") (class "Default")
      (node (ref "D5") (pin "1") (pinfunction "C_1") (pintype "passive"))
      (node (ref "R4") (pin "2") (pinfunction "2_2") (pintype "passive"))
    )
    (net (code "45") (name "Net-(D6-C)") (class "Default")
      (node (ref "D6") (pin "2") (pinfunction "C_2") (pintype "passive"))
      (node (ref "R6") (pin "2") (pinfunction "2_2") (pintype "passive"))
    )
    (net (code "46") (name "Net-(D7-A)") (class "Default")
      (node (ref "D7") (pin "2") (pinfunction "A_2") (pintype "passive"))
      (node (ref "Q2") (pin "1") (pinfunction "G_1") (pintype "passive"))
      (node (ref "R9") (pin "1") (pinfunction "1_1") (pintype "passive"))
    )
    (net (code "47") (name "Net-(Q3-VS)") (class "Default")
      (node (ref "C17") (pin "2") (pinfunction "2_2") (pintype "passive"))
      (node (ref "Q3") (pin "3") (pinfunction "VS_3") (pintype "power_in"))
    )
    (net (code "48") (name "unconnected-(D5-A-Pad2)") (class "Default")
      (node (ref "D5") (pin "2") (pinfunction "A_2") (pintype "passive"))
    )
    (net (code "49") (name "unconnected-(Q1-D-Pad3)") (class "Default")
      (node (ref "Q1") (pin "3") (pinfunction "D_3") (pintype "passive"))
    )
    (net (code "50") (name "unconnected-(Q2-D-Pad3)") (class "Default")
      (node (ref "Q2") (pin "3") (pinfunction "D_3") (pintype "passive"))
    )
    (net (code "51") (name "unconnected-(R7-Pad2)") (class "Default")
      (node (ref "R7") (pin "2") (pinfunction "2_2") (pintype "passive"))
    )
    (net (code "52") (name "unconnected-(SW1-Pad3)") (class "Default")
      (node (ref "SW1") (pin "3") (pinfunction "3_3") (pintype "passive+no_connect"))
    )
    (net (code "53") (name "unconnected-(SW2-Pad1)") (class "Default")
      (node (ref "SW2") (pin "1") (pinfunction "1_1") (pintype "passive"))
    )
    (net (code "54") (name "unconnected-(SW2-Pad3)") (class "Default")
      (node (ref "SW2") (pin "3") (pinfunction "3_3") (pintype "passive"))
    )
    (net (code "55") (name "unconnected-(SW3-Pad1)") (class "Default")
      (node (ref "SW3") (pin "1") (pinfunction "1_1") (pintype "passive"))
    )
    (net (code "56") (name "unconnected-(SW3-Pad3)") (class "Default")
      (node (ref "SW3") (pin "3") (pinfunction "3_3") (pintype "passive"))
    )
    (net (code "57") (name "unconnected-(U1A-PA11-Pad32)") (class "Default")
      (node (ref "U1") (pin "32") (pinfunction "PA11_32") (pintype "bidirectional+no_connect"))
    )
    (net (code "58") (name "unconnected-(U1A-PA12-Pad33)") (class "Default")
      (node (ref "U1") (pin "33") (pinfunction "PA12_33") (pintype "bidirectional+no_connect"))
    )
    (net (code "59") (name "unconnected-(U1A-PA15-Pad38)") (class "Default")
      (node (ref "U1") (pin "38") (pinfunction "PA15_38") (pintype "bidirectional+no_connect"))
    )
    (net (code "60") (name "unconnected-(U1A-PB1-Pad19)") (class "Default")
      (node (ref "U1") (pin "19") (pinfunction "PB1_19") (pintype "bidirectional+no_connect"))
    )
    (net (code "61") (name "unconnected-(U1A-PB2-Pad20)") (class "Default")
      (node (ref "U1") (pin "20") (pinfunction "PB2_20") (pintype "bidirectional+no_connect"))
    )
    (net (code "62") (name "unconnected-(U1A-PB3-Pad39)") (class "Default")
      (node (ref "U1") (pin "39") (pinfunction "PB3_39") (pintype "bidirectional+no_connect"))
    )
    (net (code "63") (name "unconnected-(U1A-PB12-Pad25)") (class "Default")
      (node (ref "U1") (pin "25") (pinfunction "PB12_25") (pintype "bidirectional+no_connect"))
    )
    (net (code "64") (name "unconnected-(U1A-PB13-Pad26)") (class "Default")
      (node (ref "U1") (pin "26") (pinfunction "PB13_26") (pintype "bidirectional+no_connect"))
    )
    (net (code "65") (name "unconnected-(U1A-PB14-Pad27)") (class "Default")
      (node (ref "U1") (pin "27") (pinfunction "PB14_27") (pintype "bidirectional+no_connect"))
    )
    (net (code "66") (name "unconnected-(U1A-PB15-Pad28)") (class "Default")
      (node (ref "U1") (pin "28") (pinfunction "PB15_28") (pintype "bidirectional+no_connect"))
    )
    (net (code "67") (name "unconnected-(U2-TAB-Pad6)") (class "Default")
      (node (ref "U2") (pin "6") (pinfunction "TAB_6") (pintype "power_in+no_connect"))
    )
  )
)
